# Control.net
KiCad netlist of a schematic drawn in Altium Designer
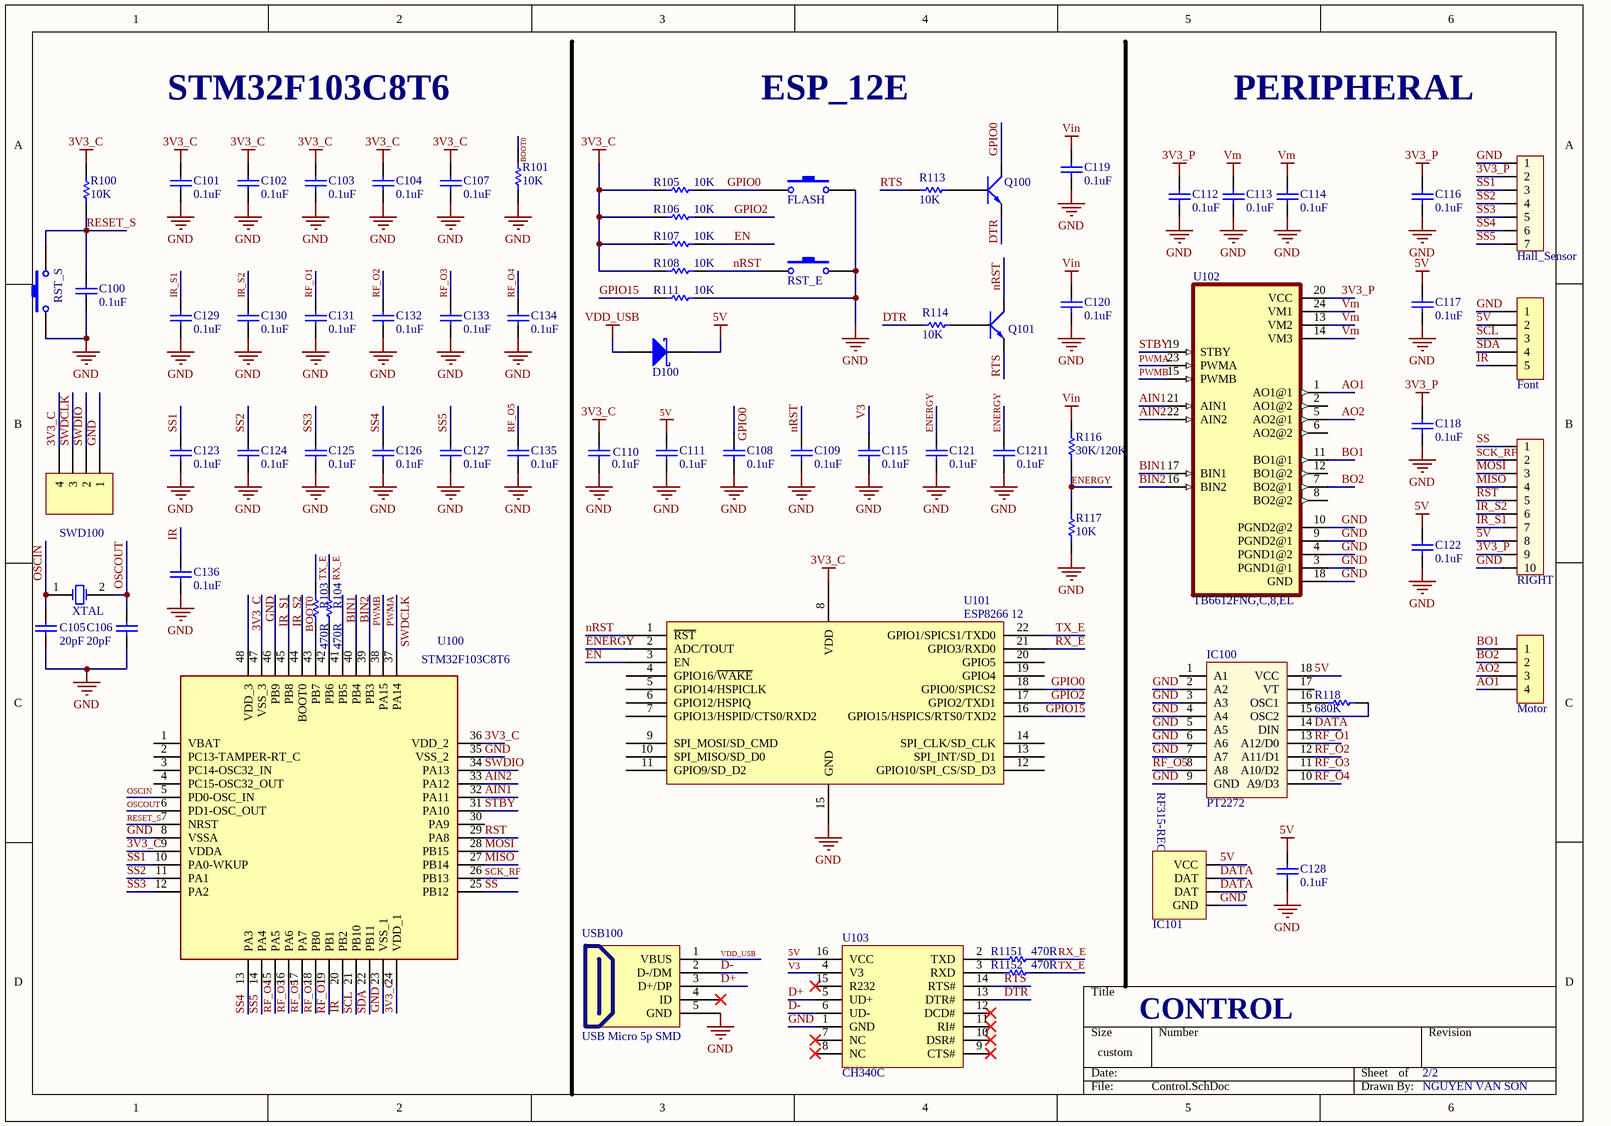
[diagram p0: Control.SchDoc]

(export (version "E")
  (design (tool "Eeschema 10.0.6"))
  (components
    (comp (ref "C100")
      (value "0.1uF")
      (footprint "CAP-SM-0603")
      (description "Capacitor")
      (fields (field (name "Comment") "Cap Non-Pol SMD"))
      (libsource (lib "PIF_Library") (part "Cap Non-Pol SMD"))
    )
    (comp (ref "C101")
      (value "0.1uF")
      (footprint "CAP-SM-0603")
      (description "Capacitor")
      (fields (field (name "Comment") "Cap Non-Pol SMD"))
      (libsource (lib "PIF_Library") (part "Cap Non-Pol SMD"))
    )
    (comp (ref "C102")
      (value "0.1uF")
      (footprint "CAP-SM-0603")
      (description "Capacitor")
      (fields (field (name "Comment") "Cap Non-Pol SMD"))
      (libsource (lib "PIF_Library") (part "Cap Non-Pol SMD"))
    )
    (comp (ref "C103")
      (value "0.1uF")
      (footprint "CAP-SM-0603")
      (description "Capacitor")
      (fields (field (name "Comment") "Cap Non-Pol SMD"))
      (libsource (lib "PIF_Library") (part "Cap Non-Pol SMD"))
    )
    (comp (ref "C104")
      (value "0.1uF")
      (footprint "CAP-SM-0603")
      (description "Capacitor")
      (fields (field (name "Comment") "Cap Non-Pol SMD"))
      (libsource (lib "PIF_Library") (part "Cap Non-Pol SMD"))
    )
    (comp (ref "C105")
      (value "20pF")
      (footprint "CAP-SM-0603")
      (description "Capacitor")
      (fields (field (name "Comment") "Cap Non-Pol SMD"))
      (libsource (lib "PIF_Library") (part "Cap Non-Pol SMD"))
    )
    (comp (ref "C106")
      (value "20pF")
      (footprint "CAP-SM-0603")
      (description "Capacitor")
      (fields (field (name "Comment") "Cap Non-Pol SMD"))
      (libsource (lib "PIF_Library") (part "Cap Non-Pol SMD"))
    )
    (comp (ref "C107")
      (value "0.1uF")
      (footprint "CAP-SM-0603")
      (description "Capacitor")
      (fields (field (name "Comment") "Cap Non-Pol SMD"))
      (libsource (lib "PIF_Library") (part "Cap Non-Pol SMD"))
    )
    (comp (ref "C108")
      (value "0.1uF")
      (footprint "CAP-SM-0603")
      (description "Capacitor")
      (fields (field (name "Comment") "Cap Non-Pol SMD"))
      (libsource (lib "PIF_Library") (part "Cap Non-Pol SMD"))
    )
    (comp (ref "C109")
      (value "0.1uF")
      (footprint "CAP-SM-0603")
      (description "Capacitor")
      (fields (field (name "Comment") "Cap Non-Pol SMD"))
      (libsource (lib "PIF_Library") (part "Cap Non-Pol SMD"))
    )
    (comp (ref "C110")
      (value "0.1uF")
      (footprint "CAP-SM-0603")
      (description "Capacitor")
      (fields (field (name "Comment") "Cap Non-Pol SMD"))
      (libsource (lib "PIF_Library") (part "Cap Non-Pol SMD"))
    )
    (comp (ref "C111")
      (value "0.1uF")
      (footprint "CAP-SM-0603")
      (description "Capacitor")
      (fields (field (name "Comment") "Cap Non-Pol SMD"))
      (libsource (lib "PIF_Library") (part "Cap Non-Pol SMD"))
    )
    (comp (ref "C112")
      (value "0.1uF")
      (footprint "CAP-SM-0603")
      (description "Capacitor")
      (fields (field (name "Comment") "Cap Non-Pol SMD"))
      (libsource (lib "PIF_Library") (part "Cap Non-Pol SMD"))
    )
    (comp (ref "C113")
      (value "0.1uF")
      (footprint "CAP-SM-0603")
      (description "Capacitor")
      (fields (field (name "Comment") "Cap Non-Pol SMD"))
      (libsource (lib "PIF_Library") (part "Cap Non-Pol SMD"))
    )
    (comp (ref "C114")
      (value "0.1uF")
      (footprint "CAP-SM-0603")
      (description "Capacitor")
      (fields (field (name "Comment") "Cap Non-Pol SMD"))
      (libsource (lib "PIF_Library") (part "Cap Non-Pol SMD"))
    )
    (comp (ref "C115")
      (value "0.1uF")
      (footprint "CAP-SM-0603")
      (description "Capacitor")
      (fields (field (name "Comment") "Cap Non-Pol SMD"))
      (libsource (lib "PIF_Library") (part "Cap Non-Pol SMD"))
    )
    (comp (ref "C116")
      (value "0.1uF")
      (footprint "CAP-SM-0603")
      (description "Capacitor")
      (fields (field (name "Comment") "Cap Non-Pol SMD"))
      (libsource (lib "PIF_Library") (part "Cap Non-Pol SMD"))
    )
    (comp (ref "C117")
      (value "0.1uF")
      (footprint "CAP-SM-0603")
      (description "Capacitor")
      (fields (field (name "Comment") "Cap Non-Pol SMD"))
      (libsource (lib "PIF_Library") (part "Cap Non-Pol SMD"))
    )
    (comp (ref "C118")
      (value "0.1uF")
      (footprint "CAP-SM-0603")
      (description "Capacitor")
      (fields (field (name "Comment") "Cap Non-Pol SMD"))
      (libsource (lib "PIF_Library") (part "Cap Non-Pol SMD"))
    )
    (comp (ref "C119")
      (value "0.1uF")
      (footprint "CAP-SM-0603")
      (description "Capacitor")
      (fields (field (name "Comment") "Cap Non-Pol SMD"))
      (libsource (lib "PIF_Library") (part "Cap Non-Pol SMD"))
    )
    (comp (ref "C120")
      (value "0.1uF")
      (footprint "CAP-SM-0603")
      (description "Capacitor")
      (fields (field (name "Comment") "Cap Non-Pol SMD"))
      (libsource (lib "PIF_Library") (part "Cap Non-Pol SMD"))
    )
    (comp (ref "C121")
      (value "0.1uF")
      (footprint "CAP-SM-0603")
      (description "Capacitor")
      (fields (field (name "Comment") "Cap Non-Pol SMD"))
      (libsource (lib "PIF_Library") (part "Cap Non-Pol SMD"))
    )
    (comp (ref "C122")
      (value "0.1uF")
      (footprint "CAP-SM-0603")
      (description "Capacitor")
      (fields (field (name "Comment") "Cap Non-Pol SMD"))
      (libsource (lib "PIF_Library") (part "Cap Non-Pol SMD"))
    )
    (comp (ref "C123")
      (value "0.1uF")
      (footprint "CAP-SM-0603")
      (description "Capacitor")
      (fields (field (name "Comment") "Cap Non-Pol SMD"))
      (libsource (lib "PIF_Library") (part "Cap Non-Pol SMD"))
    )
    (comp (ref "C124")
      (value "0.1uF")
      (footprint "CAP-SM-0603")
      (description "Capacitor")
      (fields (field (name "Comment") "Cap Non-Pol SMD"))
      (libsource (lib "PIF_Library") (part "Cap Non-Pol SMD"))
    )
    (comp (ref "C125")
      (value "0.1uF")
      (footprint "CAP-SM-0603")
      (description "Capacitor")
      (fields (field (name "Comment") "Cap Non-Pol SMD"))
      (libsource (lib "PIF_Library") (part "Cap Non-Pol SMD"))
    )
    (comp (ref "C126")
      (value "0.1uF")
      (footprint "CAP-SM-0603")
      (description "Capacitor")
      (fields (field (name "Comment") "Cap Non-Pol SMD"))
      (libsource (lib "PIF_Library") (part "Cap Non-Pol SMD"))
    )
    (comp (ref "C127")
      (value "0.1uF")
      (footprint "CAP-SM-0603")
      (description "Capacitor")
      (fields (field (name "Comment") "Cap Non-Pol SMD"))
      (libsource (lib "PIF_Library") (part "Cap Non-Pol SMD"))
    )
    (comp (ref "C128")
      (value "0.1uF")
      (footprint "CAP-SM-0603")
      (description "Capacitor")
      (fields (field (name "Comment") "Cap Non-Pol SMD"))
      (libsource (lib "PIF_Library") (part "Cap Non-Pol SMD"))
    )
    (comp (ref "C129")
      (value "0.1uF")
      (footprint "CAP-SM-0603")
      (description "Capacitor")
      (fields (field (name "Comment") "Cap Non-Pol SMD"))
      (libsource (lib "PIF_Library") (part "Cap Non-Pol SMD"))
    )
    (comp (ref "C130")
      (value "0.1uF")
      (footprint "CAP-SM-0603")
      (description "Capacitor")
      (fields (field (name "Comment") "Cap Non-Pol SMD"))
      (libsource (lib "PIF_Library") (part "Cap Non-Pol SMD"))
    )
    (comp (ref "C131")
      (value "0.1uF")
      (footprint "CAP-SM-0603")
      (description "Capacitor")
      (fields (field (name "Comment") "Cap Non-Pol SMD"))
      (libsource (lib "PIF_Library") (part "Cap Non-Pol SMD"))
    )
    (comp (ref "C132")
      (value "0.1uF")
      (footprint "CAP-SM-0603")
      (description "Capacitor")
      (fields (field (name "Comment") "Cap Non-Pol SMD"))
      (libsource (lib "PIF_Library") (part "Cap Non-Pol SMD"))
    )
    (comp (ref "C133")
      (value "0.1uF")
      (footprint "CAP-SM-0603")
      (description "Capacitor")
      (fields (field (name "Comment") "Cap Non-Pol SMD"))
      (libsource (lib "PIF_Library") (part "Cap Non-Pol SMD"))
    )
    (comp (ref "C134")
      (value "0.1uF")
      (footprint "CAP-SM-0603")
      (description "Capacitor")
      (fields (field (name "Comment") "Cap Non-Pol SMD"))
      (libsource (lib "PIF_Library") (part "Cap Non-Pol SMD"))
    )
    (comp (ref "C135")
      (value "0.1uF")
      (footprint "CAP-SM-0603")
      (description "Capacitor")
      (fields (field (name "Comment") "Cap Non-Pol SMD"))
      (libsource (lib "PIF_Library") (part "Cap Non-Pol SMD"))
    )
    (comp (ref "C136")
      (value "0.1uF")
      (footprint "CAP-SM-0603")
      (description "Capacitor")
      (fields (field (name "Comment") "Cap Non-Pol SMD"))
      (libsource (lib "PIF_Library") (part "Cap Non-Pol SMD"))
    )
    (comp (ref "C1211")
      (value "0.1uF")
      (footprint "CAP-SM-0603")
      (description "Capacitor")
      (fields (field (name "Comment") "Cap Non-Pol SMD"))
      (libsource (lib "PIF_Library") (part "Cap Non-Pol SMD"))
    )
    (comp (ref "D100")
      (value "D Schottky")
      (footprint "SS34")
      (description "Schottky Diode")
      (fields (field (name "PUBLISHER") "Altium Limited"))
      (libsource (lib "PIF_Library") (part "D Schottky"))
    )
    (comp (ref "FLASH")
      (value "Tact SW - 2Pin")
      (footprint "SW-SMD")
      (description "Switch button 2 pin")
      (libsource (lib "PIF_Library") (part "Tact SW - 2Pin"))
    )
    (comp (ref "H100")
      (value "Hall_Sensor")
      (footprint "Header 7P DC 2.54")
      (description "Cắm")
      (libsource (lib "Altium_Lib_by_KhueNguyenCreator") (part "Header 7P 2.54 Duc Cong"))
    )
    (comp (ref "H101")
      (value "Font")
      (footprint "Header 5P DC 2.54")
      (description "Cắm")
      (libsource (lib "Altium_Lib_by_KhueNguyenCreator") (part "Header 5P 2.54 Duc Cong"))
    )
    (comp (ref "H102")
      (value "RIGHT")
      (footprint "XH2.54M-10")
      (description "Cắm")
      (libsource (lib "Altium_Lib_by_KhueNguyenCreator") (part "Header 10P 2.54 Duc Thang"))
    )
    (comp (ref "H104")
      (value "Motor")
      (footprint "JP 1x4 DT")
      (description "Cắm")
      (libsource (lib "Altium_Lib_by_KhueNguyenCreator") (part "Header 4P 2.54 Duc Cong"))
    )
    (comp (ref "IC100")
      (value "PT2272")
      (footprint "DIP18")
      (description "Remote Control Decoder")
      (libsource (lib "TechMT.VN_Lib_Project v2") (part "PT2272"))
    )
    (comp (ref "IC101")
      (value "RF315-RECEIVE-NOIC")
      (footprint "RF315-RECEIVE-NOIC")
      (fields
        (field (name "MANUFACTURER") "Würth Elektronik eiSos GmbH")
        (field (name "PARTNO") "613004143121")
        (field (name "CREATED BY") "Karrer Zheng")
      )
      (libsource (lib "TechMT.VN_Lib_Project v2") (part "RF315-RECEIVE-NOIC"))
    )
    (comp (ref "Q100")
      (value "HF")
      (footprint "SOT23")
      (description "NPN transistor")
      (libsource (lib "Altium_Lib_by_KhueNguyenCreator") (part "C1815 HF SMD"))
    )
    (comp (ref "Q101")
      (value "HF")
      (footprint "SOT23")
      (description "NPN transistor")
      (libsource (lib "Altium_Lib_by_KhueNguyenCreator") (part "C1815 HF SMD"))
    )
    (comp (ref "R100")
      (value "10K")
      (footprint "RES-SM-0603")
      (description "Resistor")
      (fields (field (name "Comment") "RESISTOR SMD"))
      (libsource (lib "PIF_Library") (part "RESISTOR SMD"))
    )
    (comp (ref "R101")
      (value "10K")
      (footprint "RES-SM-0603")
      (description "Resistor")
      (fields (field (name "Comment") "RESISTOR SMD"))
      (libsource (lib "PIF_Library") (part "RESISTOR SMD"))
    )
    (comp (ref "R103")
      (value "470R")
      (footprint "RES-SM-0603")
      (description "Resistor")
      (fields (field (name "Comment") "RESISTOR SMD"))
      (libsource (lib "PIF_Library") (part "RESISTOR SMD"))
    )
    (comp (ref "R104")
      (value "470R")
      (footprint "RES-SM-0603")
      (description "Resistor")
      (fields (field (name "Comment") "RESISTOR SMD"))
      (libsource (lib "PIF_Library") (part "RESISTOR SMD"))
    )
    (comp (ref "R105")
      (value "10K")
      (footprint "RES-SM-0603")
      (description "Resistor")
      (fields (field (name "Comment") "RESISTOR SMD"))
      (libsource (lib "PIF_Library") (part "RESISTOR SMD"))
    )
    (comp (ref "R106")
      (value "10K")
      (footprint "RES-SM-0603")
      (description "Resistor")
      (fields (field (name "Comment") "RESISTOR SMD"))
      (libsource (lib "PIF_Library") (part "RESISTOR SMD"))
    )
    (comp (ref "R107")
      (value "10K")
      (footprint "RES-SM-0603")
      (description "Resistor")
      (fields (field (name "Comment") "RESISTOR SMD"))
      (libsource (lib "PIF_Library") (part "RESISTOR SMD"))
    )
    (comp (ref "R108")
      (value "10K")
      (footprint "RES-SM-0603")
      (description "Resistor")
      (fields (field (name "Comment") "RESISTOR SMD"))
      (libsource (lib "PIF_Library") (part "RESISTOR SMD"))
    )
    (comp (ref "R111")
      (value "10K")
      (footprint "RES-SM-0603")
      (description "Resistor")
      (fields (field (name "Comment") "RESISTOR SMD"))
      (libsource (lib "PIF_Library") (part "RESISTOR SMD"))
    )
    (comp (ref "R113")
      (value "10K")
      (footprint "RES-SM-0603")
      (description "Resistor")
      (fields (field (name "Comment") "RESISTOR SMD"))
      (libsource (lib "PIF_Library") (part "RESISTOR SMD"))
    )
    (comp (ref "R114")
      (value "10K")
      (footprint "RES-SM-0603")
      (description "Resistor")
      (fields (field (name "Comment") "RESISTOR SMD"))
      (libsource (lib "PIF_Library") (part "RESISTOR SMD"))
    )
    (comp (ref "R116")
      (value "30K/120K")
      (footprint "RES-SM-0603")
      (description "Resistor")
      (fields (field (name "Comment") "RESISTOR SMD"))
      (libsource (lib "PIF_Library") (part "RESISTOR SMD"))
    )
    (comp (ref "R117")
      (value "10K")
      (footprint "RES-SM-0603")
      (description "Resistor")
      (fields (field (name "Comment") "RESISTOR SMD"))
      (libsource (lib "PIF_Library") (part "RESISTOR SMD"))
    )
    (comp (ref "R118")
      (value "680K")
      (footprint "RES-SM-0603")
      (description "Resistor")
      (fields (field (name "Comment") "RESISTOR SMD"))
      (libsource (lib "PIF_Library") (part "RESISTOR SMD"))
    )
    (comp (ref "R1151")
      (value "470R")
      (footprint "RES-SM-0603")
      (description "Resistor")
      (fields (field (name "Comment") "RESISTOR SMD"))
      (libsource (lib "PIF_Library") (part "RESISTOR SMD"))
    )
    (comp (ref "R1152")
      (value "470R")
      (footprint "RES-SM-0603")
      (description "Resistor")
      (fields (field (name "Comment") "RESISTOR SMD"))
      (libsource (lib "PIF_Library") (part "RESISTOR SMD"))
    )
    (comp (ref "RST_E")
      (value "Tact SW - 2Pin")
      (footprint "SW-SMD")
      (description "Switch button 2 pin")
      (libsource (lib "PIF_Library") (part "Tact SW - 2Pin"))
    )
    (comp (ref "RST_S")
      (value "Tact SW - 2Pin")
      (footprint "SW-SMD")
      (description "Switch button 2 pin")
      (libsource (lib "PIF_Library") (part "Tact SW - 2Pin"))
    )
    (comp (ref "SWD100")
      (value "Header 4H")
      (footprint "JP4")
      (description "Header, 4-Pin, Right Angle")
      (fields (field (name "PUBLISHER") "Altium Limited"))
      (libsource (lib "PIF_Library") (part "Header 4H"))
    )
    (comp (ref "U100")
      (value "STM32F103C8T6")
      (footprint "LQFP-48_19.6_393_58X11_SMD")
      (description "ARM® Cortex®-M3 STM32F1 Microcontroller IC 32-Bit 72MHz 64KB (64K x 8) FLASH 48-LQFP (7x7)")
      (fields (field (name "MANUFACTURER") "STMicroelectronics"))
      (libsource (lib "Altium_Lib_by_KhueNguyenCreator") (part "IC_STM32F103C8T6"))
    )
    (comp (ref "U101")
      (value "ESP8266 12")
      (footprint "ESP8266 12")
      (description "ESP8266 12 22 Pin")
      (libsource (lib "Altium_Lib_by_KhueNguyenCreator") (part "ESP8266 12"))
    )
    (comp (ref "U102")
      (value "TB6612FNG,C,8,EL")
      (footprint "SOP65P760X160-24N")
      (description "- Motor Driver Power MOSFET Parallel 24-SSOP")
      (fields (field (name "MF") "Toshiba"))
      (libsource (lib "TB6612FNG_C_8_EL") (part "TB6612FNG,C,8,EL"))
    )
    (comp (ref "U103")
      (value "CH340C")
      (footprint "SOIC16_50_284_25X90_SMT")
      (description "USB Bridge, USB to UART USB 2.0 UART Interface")
      (fields (field (name "MANUFACTURER") "Olimex"))
      (libsource (lib "Altium_Lib_by_KhueNguyenCreator") (part "IC_CH340C"))
    )
    (comp (ref "USB100")
      (value "USB Micro 5p SMD")
      (footprint "USB Micro 5p SMD")
      (description "USB Type B")
      (libsource (lib "Altium_Lib_by_KhueNguyenCreator") (part "USB Micro 5p SMD"))
    )
    (comp (ref "XTAL")
      (value "XTAL")
      (footprint "XT2")
      (description "Crystal Oscillator")
      (fields (field (name "PUBLISHER") "Altium Limited"))
      (libsource (lib "PIF_Library") (part "XTAL"))
    )
  )
  (nets
    (net (code "1") (name "/AIN1") (class "Default")
      (node (ref "U100") (pin "32") (pinfunction "PA11_32") (pintype "passive"))
      (node (ref "U102") (pin "21") (pinfunction "AIN1_21") (pintype "input"))
    )
    (net (code "2") (name "/AIN2") (class "Default")
      (node (ref "U100") (pin "33") (pinfunction "PA12_33") (pintype "passive"))
      (node (ref "U102") (pin "22") (pinfunction "AIN2_22") (pintype "input"))
    )
    (net (code "3") (name "/AO1") (class "Default")
      (node (ref "H104") (pin "4") (pinfunction "4_4") (pintype "passive"))
      (node (ref "U102") (pin "1") (pinfunction "AO1@1_1") (pintype "output"))
    )
    (net (code "4") (name "/AO2") (class "Default")
      (node (ref "H104") (pin "3") (pinfunction "3_3") (pintype "passive"))
      (node (ref "U102") (pin "5") (pinfunction "AO2@1_5") (pintype "output"))
    )
    (net (code "5") (name "/BIN1") (class "Default")
      (node (ref "U100") (pin "41") (pinfunction "PB5_41") (pintype "passive"))
      (node (ref "U102") (pin "17") (pinfunction "BIN1_17") (pintype "input"))
    )
    (net (code "6") (name "/BIN2") (class "Default")
      (node (ref "U100") (pin "40") (pinfunction "PB4_40") (pintype "passive"))
      (node (ref "U102") (pin "16") (pinfunction "BIN2_16") (pintype "input"))
    )
    (net (code "7") (name "/BO1") (class "Default")
      (node (ref "H104") (pin "1") (pinfunction "1_1") (pintype "passive"))
      (node (ref "U102") (pin "11") (pinfunction "BO1@1_11") (pintype "output"))
    )
    (net (code "8") (name "/BO2") (class "Default")
      (node (ref "H104") (pin "2") (pinfunction "2_2") (pintype "passive"))
      (node (ref "U102") (pin "7") (pinfunction "BO2@1_7") (pintype "output"))
    )
    (net (code "9") (name "/BOOT0") (class "Default")
      (node (ref "R101") (pin "1") (pinfunction "1_1") (pintype "passive"))
      (node (ref "U100") (pin "44") (pinfunction "BOOT0_44") (pintype "passive"))
    )
    (net (code "10") (name "/D+") (class "Default")
      (node (ref "U103") (pin "5") (pinfunction "UD+_5") (pintype "passive"))
      (node (ref "USB100") (pin "3") (pinfunction "D+/DP_3") (pintype "passive"))
    )
    (net (code "11") (name "/D-") (class "Default")
      (node (ref "U103") (pin "6") (pinfunction "UD-_6") (pintype "passive"))
      (node (ref "USB100") (pin "2") (pinfunction "D-/DM_2") (pintype "passive"))
    )
    (net (code "12") (name "/DATA") (class "Default")
      (node (ref "IC100") (pin "14") (pinfunction "DIN_14") (pintype "passive"))
      (node (ref "IC101") (pin "2") (pinfunction "DAT_2") (pintype "passive"))
      (node (ref "IC101") (pin "3") (pinfunction "DAT_3") (pintype "passive"))
    )
    (net (code "13") (name "/DTR") (class "Default")
      (node (ref "Q100") (pin "2") (pinfunction "E_2") (pintype "passive"))
      (node (ref "R114") (pin "1") (pinfunction "1_1") (pintype "passive"))
      (node (ref "U103") (pin "13") (pinfunction "DTR#_13") (pintype "passive"))
    )
    (net (code "14") (name "/EN") (class "Default")
      (node (ref "R107") (pin "1") (pinfunction "1_1") (pintype "passive"))
      (node (ref "U101") (pin "3") (pinfunction "EN_3") (pintype "passive"))
    )
    (net (code "15") (name "/ENERGY") (class "Default")
      (node (ref "C121") (pin "2") (pinfunction "2_2") (pintype "passive"))
      (node (ref "C1211") (pin "2") (pinfunction "2_2") (pintype "passive"))
      (node (ref "R116") (pin "1") (pinfunction "1_1") (pintype "passive"))
      (node (ref "R117") (pin "2") (pinfunction "2_2") (pintype "passive"))
      (node (ref "U101") (pin "2") (pinfunction "ADC/TOUT_2") (pintype "passive"))
    )
    (net (code "16") (name "/GPIO0") (class "Default")
      (node (ref "C108") (pin "2") (pinfunction "2_2") (pintype "passive"))
      (node (ref "FLASH") (pin "2") (pinfunction "2_2") (pintype "passive"))
      (node (ref "Q100") (pin "3") (pinfunction "C_3") (pintype "passive"))
      (node (ref "R105") (pin "1") (pinfunction "1_1") (pintype "passive"))
      (node (ref "U101") (pin "18") (pinfunction "GPIO0/SPICS2_18") (pintype "passive"))
    )
    (net (code "17") (name "/GPIO2") (class "Default")
      (node (ref "R106") (pin "1") (pinfunction "1_1") (pintype "passive"))
      (node (ref "U101") (pin "17") (pinfunction "GPIO2/TXD1_17") (pintype "passive"))
    )
    (net (code "18") (name "/GPIO15") (class "Default")
      (node (ref "R111") (pin "2") (pinfunction "2_2") (pintype "passive"))
      (node (ref "U101") (pin "16") (pinfunction "GPIO15/HSPICS/RTS0/TXD2_16") (pintype "passive"))
    )
    (net (code "19") (name "/IR") (class "Default")
      (node (ref "C136") (pin "2") (pinfunction "2_2") (pintype "passive"))
      (node (ref "H101") (pin "5") (pinfunction "5_5") (pintype "passive"))
      (node (ref "U100") (pin "20") (pinfunction "PB2_20") (pintype "passive"))
    )
    (net (code "20") (name "/IR_S1") (class "Default")
      (node (ref "C129") (pin "2") (pinfunction "2_2") (pintype "passive"))
      (node (ref "H102") (pin "7") (pinfunction "7_7") (pintype "passive"))
      (node (ref "U100") (pin "46") (pinfunction "PB9_46") (pintype "passive"))
    )
    (net (code "21") (name "/IR_S2") (class "Default")
      (node (ref "C130") (pin "2") (pinfunction "2_2") (pintype "passive"))
      (node (ref "H102") (pin "6") (pinfunction "6_6") (pintype "passive"))
      (node (ref "U100") (pin "45") (pinfunction "PB8_45") (pintype "passive"))
    )
    (net (code "22") (name "/MISO") (class "Default")
      (node (ref "H102") (pin "4") (pinfunction "4_4") (pintype "passive"))
      (node (ref "U100") (pin "27") (pinfunction "PB14_27") (pintype "passive"))
    )
    (net (code "23") (name "/MOSI") (class "Default")
      (node (ref "H102") (pin "3") (pinfunction "3_3") (pintype "passive"))
      (node (ref "U100") (pin "28") (pinfunction "PB15_28") (pintype "passive"))
    )
    (net (code "24") (name "/OSCIN") (class "Default")
      (node (ref "C105") (pin "2") (pinfunction "2_2") (pintype "passive"))
      (node (ref "U100") (pin "5") (pinfunction "PD0-OSC_IN_5") (pintype "passive"))
      (node (ref "XTAL") (pin "1") (pinfunction "OSC1_1") (pintype "passive"))
    )
    (net (code "25") (name "/OSCOUT") (class "Default")
      (node (ref "C106") (pin "2") (pinfunction "2_2") (pintype "passive"))
      (node (ref "U100") (pin "6") (pinfunction "PD1-OSC_OUT_6") (pintype "passive"))
      (node (ref "XTAL") (pin "2") (pinfunction "OSC2_2") (pintype "passive"))
    )
    (net (code "26") (name "/PWMA") (class "Default")
      (node (ref "U100") (pin "38") (pinfunction "PA15_38") (pintype "passive"))
      (node (ref "U102") (pin "23") (pinfunction "PWMA_23") (pintype "input"))
    )
    (net (code "27") (name "/PWMB") (class "Default")
      (node (ref "U100") (pin "39") (pinfunction "PB3_39") (pintype "passive"))
      (node (ref "U102") (pin "15") (pinfunction "PWMB_15") (pintype "input"))
    )
    (net (code "28") (name "/RESET_S") (class "Default")
      (node (ref "C100") (pin "2") (pinfunction "2_2") (pintype "passive"))
      (node (ref "R100") (pin "1") (pinfunction "1_1") (pintype "passive"))
      (node (ref "RST_S") (pin "2") (pinfunction "2_2") (pintype "passive"))
      (node (ref "U100") (pin "7") (pinfunction "NRST_7") (pintype "passive"))
    )
    (net (code "29") (name "/RF_O1") (class "Default")
      (node (ref "C131") (pin "2") (pinfunction "2_2") (pintype "passive"))
      (node (ref "IC100") (pin "13") (pinfunction "A12/D0_13") (pintype "passive"))
      (node (ref "U100") (pin "19") (pinfunction "PB1_19") (pintype "passive"))
    )
    (net (code "30") (name "/RF_O2") (class "Default")
      (node (ref "C132") (pin "2") (pinfunction "2_2") (pintype "passive"))
      (node (ref "IC100") (pin "12") (pinfunction "A11/D1_12") (pintype "passive"))
      (node (ref "U100") (pin "18") (pinfunction "PB0_18") (pintype "passive"))
    )
    (net (code "31") (name "/RF_O3") (class "Default")
      (node (ref "C133") (pin "2") (pinfunction "2_2") (pintype "passive"))
      (node (ref "IC100") (pin "11") (pinfunction "A10/D2_11") (pintype "passive"))
      (node (ref "U100") (pin "16") (pinfunction "PA6_16") (pintype "passive"))
    )
    (net (code "32") (name "/RF_O4") (class "Default")
      (node (ref "C134") (pin "2") (pinfunction "2_2") (pintype "passive"))
      (node (ref "IC100") (pin "10") (pinfunction "A9/D3_10") (pintype "passive"))
      (node (ref "U100") (pin "15") (pinfunction "PA5_15") (pintype "passive"))
    )
    (net (code "33") (name "/RF_O5") (class "Default")
      (node (ref "C135") (pin "2") (pinfunction "2_2") (pintype "passive"))
      (node (ref "IC100") (pin "8") (pinfunction "A8_8") (pintype "passive"))
      (node (ref "U100") (pin "17") (pinfunction "PA7_17") (pintype "passive"))
    )
    (net (code "34") (name "/RST") (class "Default")
      (node (ref "H102") (pin "5") (pinfunction "5_5") (pintype "passive"))
      (node (ref "U100") (pin "29") (pinfunction "PA8_29") (pintype "passive"))
    )
    (net (code "35") (name "/RTS") (class "Default")
      (node (ref "Q101") (pin "2") (pinfunction "E_2") (pintype "passive"))
      (node (ref "R113") (pin "1") (pinfunction "1_1") (pintype "passive"))
      (node (ref "U103") (pin "14") (pinfunction "RTS#_14") (pintype "passive"))
    )
    (net (code "36") (name "/RX_E") (class "Default")
      (node (ref "R104") (pin "2") (pinfunction "2_2") (pintype "passive"))
      (node (ref "R1151") (pin "1") (pinfunction "1_1") (pintype "passive"))
      (node (ref "U101") (pin "21") (pinfunction "GPIO3/RXD0_21") (pintype "passive"))
    )
    (net (code "37") (name "/SCK_RF") (class "Default")
      (node (ref "H102") (pin "2") (pinfunction "2_2") (pintype "passive"))
      (node (ref "U100") (pin "26") (pinfunction "PB13_26") (pintype "passive"))
    )
    (net (code "38") (name "/SCL") (class "Default")
      (node (ref "H101") (pin "3") (pinfunction "3_3") (pintype "passive"))
      (node (ref "U100") (pin "21") (pinfunction "PB10_21") (pintype "passive"))
    )
    (net (code "39") (name "/SDA") (class "Default")
      (node (ref "H101") (pin "4") (pinfunction "4_4") (pintype "passive"))
      (node (ref "U100") (pin "22") (pinfunction "PB11_22") (pintype "passive"))
    )
    (net (code "40") (name "/SS") (class "Default")
      (node (ref "H102") (pin "1") (pinfunction "1_1") (pintype "passive"))
      (node (ref "U100") (pin "25") (pinfunction "PB12_25") (pintype "passive"))
    )
    (net (code "41") (name "/SS1") (class "Default")
      (node (ref "C123") (pin "2") (pinfunction "2_2") (pintype "passive"))
      (node (ref "H100") (pin "3") (pinfunction "3_3") (pintype "passive"))
      (node (ref "U100") (pin "10") (pinfunction "PA0-WKUP_10") (pintype "passive"))
    )
    (net (code "42") (name "/SS2") (class "Default")
      (node (ref "C124") (pin "2") (pinfunction "2_2") (pintype "passive"))
      (node (ref "H100") (pin "4") (pinfunction "4_4") (pintype "passive"))
      (node (ref "U100") (pin "11") (pinfunction "PA1_11") (pintype "passive"))
    )
    (net (code "43") (name "/SS3") (class "Default")
      (node (ref "C125") (pin "2") (pinfunction "2_2") (pintype "passive"))
      (node (ref "H100") (pin "5") (pinfunction "5_5") (pintype "passive"))
      (node (ref "U100") (pin "12") (pinfunction "PA2_12") (pintype "passive"))
    )
    (net (code "44") (name "/SS4") (class "Default")
      (node (ref "C126") (pin "2") (pinfunction "2_2") (pintype "passive"))
      (node (ref "H100") (pin "6") (pinfunction "6_6") (pintype "passive"))
      (node (ref "U100") (pin "13") (pinfunction "PA3_13") (pintype "passive"))
    )
    (net (code "45") (name "/SS5") (class "Default")
      (node (ref "C127") (pin "2") (pinfunction "2_2") (pintype "passive"))
      (node (ref "H100") (pin "7") (pinfunction "7_7") (pintype "passive"))
      (node (ref "U100") (pin "14") (pinfunction "PA4_14") (pintype "passive"))
    )
    (net (code "46") (name "/STBY") (class "Default")
      (node (ref "U100") (pin "31") (pinfunction "PA10_31") (pintype "passive"))
      (node (ref "U102") (pin "19") (pinfunction "STBY_19") (pintype "input"))
    )
    (net (code "47") (name "/SWDCLK") (class "Default")
      (node (ref "SWD100") (pin "3") (pinfunction "3_3") (pintype "passive"))
      (node (ref "U100") (pin "37") (pinfunction "PA14_37") (pintype "passive"))
    )
    (net (code "48") (name "/SWDIO") (class "Default")
      (node (ref "SWD100") (pin "2") (pinfunction "2_2") (pintype "passive"))
      (node (ref "U100") (pin "34") (pinfunction "PA13_34") (pintype "passive"))
    )
    (net (code "49") (name "/TX_E") (class "Default")
      (node (ref "R103") (pin "2") (pinfunction "2_2") (pintype "passive"))
      (node (ref "R1152") (pin "1") (pinfunction "1_1") (pintype "passive"))
      (node (ref "U101") (pin "22") (pinfunction "GPIO1/SPICS1/TXD0_22") (pintype "passive"))
    )
    (net (code "50") (name "/V3") (class "Default")
      (node (ref "C115") (pin "2") (pinfunction "2_2") (pintype "passive"))
      (node (ref "U103") (pin "4") (pinfunction "V3_4") (pintype "passive"))
    )
    (net (code "51") (name "/nRST") (class "Default")
      (node (ref "C109") (pin "2") (pinfunction "2_2") (pintype "passive"))
      (node (ref "Q101") (pin "3") (pinfunction "C_3") (pintype "passive"))
      (node (ref "R108") (pin "1") (pinfunction "1_1") (pintype "passive"))
      (node (ref "RST_E") (pin "2") (pinfunction "2_2") (pintype "passive"))
      (node (ref "U101") (pin "1") (pinfunction "~{RST}_1") (pintype "passive"))
    )
    (net (code "52") (name "3V3_C") (class "Default")
      (node (ref "C101") (pin "2") (pinfunction "2_2") (pintype "passive"))
      (node (ref "C102") (pin "2") (pinfunction "2_2") (pintype "passive"))
      (node (ref "C103") (pin "2") (pinfunction "2_2") (pintype "passive"))
      (node (ref "C104") (pin "2") (pinfunction "2_2") (pintype "passive"))
      (node (ref "C107") (pin "2") (pinfunction "2_2") (pintype "passive"))
      (node (ref "C110") (pin "2") (pinfunction "2_2") (pintype "passive"))
      (node (ref "R100") (pin "2") (pinfunction "2_2") (pintype "passive"))
      (node (ref "R105") (pin "2") (pinfunction "2_2") (pintype "passive"))
      (node (ref "R106") (pin "2") (pinfunction "2_2") (pintype "passive"))
      (node (ref "R107") (pin "2") (pinfunction "2_2") (pintype "passive"))
      (node (ref "R108") (pin "2") (pinfunction "2_2") (pintype "passive"))
      (node (ref "SWD100") (pin "4") (pinfunction "4_4") (pintype "passive"))
      (node (ref "U100") (pin "24") (pinfunction "VDD_1_24") (pintype "passive"))
      (node (ref "U100") (pin "36") (pinfunction "VDD_2_36") (pintype "passive"))
      (node (ref "U100") (pin "48") (pinfunction "VDD_3_48") (pintype "passive"))
      (node (ref "U100") (pin "9") (pinfunction "VDDA_9") (pintype "passive"))
      (node (ref "U101") (pin "8") (pinfunction "VDD_8") (pintype "passive"))
    )
    (net (code "53") (name "3V3_P") (class "Default")
      (node (ref "C112") (pin "2") (pinfunction "2_2") (pintype "passive"))
      (node (ref "C116") (pin "2") (pinfunction "2_2") (pintype "passive"))
      (node (ref "C118") (pin "2") (pinfunction "2_2") (pintype "passive"))
      (node (ref "H100") (pin "2") (pinfunction "2_2") (pintype "passive"))
      (node (ref "H102") (pin "9") (pinfunction "9_9") (pintype "passive"))
      (node (ref "U102") (pin "20") (pinfunction "VCC_20") (pintype "power_in"))
    )
    (net (code "54") (name "5V") (class "Default")
      (node (ref "C111") (pin "2") (pinfunction "2_2") (pintype "passive"))
      (node (ref "C117") (pin "2") (pinfunction "2_2") (pintype "passive"))
      (node (ref "C122") (pin "2") (pinfunction "2_2") (pintype "passive"))
      (node (ref "C128") (pin "2") (pinfunction "2_2") (pintype "passive"))
      (node (ref "D100") (pin "2") (pinfunction "K_2") (pintype "passive"))
      (node (ref "H101") (pin "2") (pinfunction "2_2") (pintype "passive"))
      (node (ref "H102") (pin "8") (pinfunction "8_8") (pintype "passive"))
      (node (ref "IC100") (pin "18") (pinfunction "VCC_18") (pintype "passive"))
      (node (ref "IC101") (pin "1") (pinfunction "VCC_1") (pintype "passive"))
      (node (ref "U103") (pin "16") (pinfunction "VCC_16") (pintype "passive"))
    )
    (net (code "55") (name "GND") (class "Default")
      (node (ref "C100") (pin "1") (pinfunction "1_1") (pintype "passive"))
      (node (ref "C101") (pin "1") (pinfunction "1_1") (pintype "passive"))
      (node (ref "C102") (pin "1") (pinfunction "1_1") (pintype "passive"))
      (node (ref "C103") (pin "1") (pinfunction "1_1") (pintype "passive"))
      (node (ref "C104") (pin "1") (pinfunction "1_1") (pintype "passive"))
      (node (ref "C105") (pin "1") (pinfunction "1_1") (pintype "passive"))
      (node (ref "C106") (pin "1") (pinfunction "1_1") (pintype "passive"))
      (node (ref "C107") (pin "1") (pinfunction "1_1") (pintype "passive"))
      (node (ref "C108") (pin "1") (pinfunction "1_1") (pintype "passive"))
      (node (ref "C109") (pin "1") (pinfunction "1_1") (pintype "passive"))
      (node (ref "C110") (pin "1") (pinfunction "1_1") (pintype "passive"))
      (node (ref "C111") (pin "1") (pinfunction "1_1") (pintype "passive"))
      (node (ref "C112") (pin "1") (pinfunction "1_1") (pintype "passive"))
      (node (ref "C113") (pin "1") (pinfunction "1_1") (pintype "passive"))
      (node (ref "C114") (pin "1") (pinfunction "1_1") (pintype "passive"))
      (node (ref "C115") (pin "1") (pinfunction "1_1") (pintype "passive"))
      (node (ref "C116") (pin "1") (pinfunction "1_1") (pintype "passive"))
      (node (ref "C117") (pin "1") (pinfunction "1_1") (pintype "passive"))
      (node (ref "C118") (pin "1") (pinfunction "1_1") (pintype "passive"))
      (node (ref "C119") (pin "1") (pinfunction "1_1") (pintype "passive"))
      (node (ref "C120") (pin "1") (pinfunction "1_1") (pintype "passive"))
      (node (ref "C121") (pin "1") (pinfunction "1_1") (pintype "passive"))
      (node (ref "C1211") (pin "1") (pinfunction "1_1") (pintype "passive"))
      (node (ref "C122") (pin "1") (pinfunction "1_1") (pintype "passive"))
      (node (ref "C123") (pin "1") (pinfunction "1_1") (pintype "passive"))
      (node (ref "C124") (pin "1") (pinfunction "1_1") (pintype "passive"))
      (node (ref "C125") (pin "1") (pinfunction "1_1") (pintype "passive"))
      (node (ref "C126") (pin "1") (pinfunction "1_1") (pintype "passive"))
      (node (ref "C127") (pin "1") (pinfunction "1_1") (pintype "passive"))
      (node (ref "C128") (pin "1") (pinfunction "1_1") (pintype "passive"))
      (node (ref "C129") (pin "1") (pinfunction "1_1") (pintype "passive"))
      (node (ref "C130") (pin "1") (pinfunction "1_1") (pintype "passive"))
      (node (ref "C131") (pin "1") (pinfunction "1_1") (pintype "passive"))
      (node (ref "C132") (pin "1") (pinfunction "1_1") (pintype "passive"))
      (node (ref "C133") (pin "1") (pinfunction "1_1") (pintype "passive"))
      (node (ref "C134") (pin "1") (pinfunction "1_1") (pintype "passive"))
      (node (ref "C135") (pin "1") (pinfunction "1_1") (pintype "passive"))
      (node (ref "C136") (pin "1") (pinfunction "1_1") (pintype "passive"))
      (node (ref "FLASH") (pin "1") (pinfunction "1_1") (pintype "passive"))
      (node (ref "H100") (pin "1") (pinfunction "1_1") (pintype "passive"))
      (node (ref "H101") (pin "1") (pinfunction "1_1") (pintype "passive"))
      (node (ref "H102") (pin "10") (pinfunction "10_10") (pintype "passive"))
      (node (ref "IC100") (pin "2") (pinfunction "A2_2") (pintype "passive"))
      (node (ref "IC100") (pin "3") (pinfunction "A3_3") (pintype "passive"))
      (node (ref "IC100") (pin "4") (pinfunction "A4_4") (pintype "passive"))
      (node (ref "IC100") (pin "5") (pinfunction "A5_5") (pintype "passive"))
      (node (ref "IC100") (pin "6") (pinfunction "A6_6") (pintype "passive"))
      (node (ref "IC100") (pin "7") (pinfunction "A7_7") (pintype "passive"))
      (node (ref "IC100") (pin "9") (pinfunction "GND_9") (pintype "passive"))
      (node (ref "IC101") (pin "4") (pinfunction "GND_4") (pintype "passive"))
      (node (ref "R101") (pin "2") (pinfunction "2_2") (pintype "passive"))
      (node (ref "R111") (pin "1") (pinfunction "1_1") (pintype "passive"))
      (node (ref "R117") (pin "1") (pinfunction "1_1") (pintype "passive"))
      (node (ref "RST_E") (pin "1") (pinfunction "1_1") (pintype "passive"))
      (node (ref "RST_S") (pin "1") (pinfunction "1_1") (pintype "passive"))
      (node (ref "SWD100") (pin "1") (pinfunction "1_1") (pintype "passive"))
      (node (ref "U100") (pin "23") (pinfunction "VSS_1_23") (pintype "passive"))
      (node (ref "U100") (pin "35") (pinfunction "VSS_2_35") (pintype "passive"))
      (node (ref "U100") (pin "47") (pinfunction "VSS_3_47") (pintype "passive"))
      (node (ref "U100") (pin "8") (pinfunction "VSSA_8") (pintype "passive"))
      (node (ref "U101") (pin "15") (pinfunction "GND_15") (pintype "passive"))
      (node (ref "U102") (pin "10") (pinfunction "PGND2@2_10") (pintype "passive"))
      (node (ref "U102") (pin "18") (pinfunction "GND_18") (pintype "passive"))
      (node (ref "U102") (pin "3") (pinfunction "PGND1@1_3") (pintype "passive"))
      (node (ref "U102") (pin "4") (pinfunction "PGND1@2_4") (pintype "passive"))
      (node (ref "U102") (pin "9") (pinfunction "PGND2@1_9") (pintype "passive"))
      (node (ref "U103") (pin "1") (pinfunction "GND_1") (pintype "passive"))
      (node (ref "USB100") (pin "5") (pinfunction "GND_5") (pintype "passive"))
    )
    (net (code "56") (name "Net-(IC100-OSC1)") (class "Default")
      (node (ref "IC100") (pin "16") (pinfunction "OSC1_16") (pintype "passive"))
      (node (ref "R118") (pin "2") (pinfunction "2_2") (pintype "passive"))
    )
    (net (code "57") (name "Net-(IC100-OSC2)") (class "Default")
      (node (ref "IC100") (pin "15") (pinfunction "OSC2_15") (pintype "passive"))
      (node (ref "R118") (pin "1") (pinfunction "1_1") (pintype "passive"))
    )
    (net (code "58") (name "Net-(Q100-B)") (class "Default")
      (node (ref "Q100") (pin "1") (pinfunction "B_1") (pintype "passive"))
      (node (ref "R113") (pin "2") (pinfunction "2_2") (pintype "passive"))
    )
    (net (code "59") (name "Net-(Q101-B)") (class "Default")
      (node (ref "Q101") (pin "1") (pinfunction "B_1") (pintype "passive"))
      (node (ref "R114") (pin "2") (pinfunction "2_2") (pintype "passive"))
    )
    (net (code "60") (name "Net-(U100-PB6)") (class "Default")
      (node (ref "R104") (pin "1") (pinfunction "1_1") (pintype "passive"))
      (node (ref "U100") (pin "42") (pinfunction "PB6_42") (pintype "passive"))
    )
    (net (code "61") (name "Net-(U100-PB7)") (class "Default")
      (node (ref "R103") (pin "1") (pinfunction "1_1") (pintype "passive"))
      (node (ref "U100") (pin "43") (pinfunction "PB7_43") (pintype "passive"))
    )
    (net (code "62") (name "Net-(U103-RXD)") (class "Default")
      (node (ref "R1152") (pin "2") (pinfunction "2_2") (pintype "passive"))
      (node (ref "U103") (pin "3") (pinfunction "RXD_3") (pintype "passive"))
    )
    (net (code "63") (name "Net-(U103-TXD)") (class "Default")
      (node (ref "R1151") (pin "2") (pinfunction "2_2") (pintype "passive"))
      (node (ref "U103") (pin "2") (pinfunction "TXD_2") (pintype "passive"))
    )
    (net (code "64") (name "VDD_USB") (class "Default")
      (node (ref "D100") (pin "1") (pinfunction "A_1") (pintype "passive"))
      (node (ref "USB100") (pin "1") (pinfunction "VBUS_1") (pintype "passive"))
    )
    (net (code "65") (name "Vin") (class "Default")
      (node (ref "C119") (pin "2") (pinfunction "2_2") (pintype "passive"))
      (node (ref "C120") (pin "2") (pinfunction "2_2") (pintype "passive"))
      (node (ref "R116") (pin "2") (pinfunction "2_2") (pintype "passive"))
    )
    (net (code "66") (name "Vm") (class "Default")
      (node (ref "C113") (pin "2") (pinfunction "2_2") (pintype "passive"))
      (node (ref "C114") (pin "2") (pinfunction "2_2") (pintype "passive"))
      (node (ref "U102") (pin "13") (pinfunction "VM2_13") (pintype "power_in"))
      (node (ref "U102") (pin "14") (pinfunction "VM3_14") (pintype "power_in"))
      (node (ref "U102") (pin "24") (pinfunction "VM1_24") (pintype "power_in"))
    )
    (net (code "67") (name "unconnected-(IC100-A1-Pad1)") (class "Default")
      (node (ref "IC100") (pin "1") (pinfunction "A1_1") (pintype "passive"))
    )
    (net (code "68") (name "unconnected-(IC100-VT-Pad17)") (class "Default")
      (node (ref "IC100") (pin "17") (pinfunction "VT_17") (pintype "passive"))
    )
    (net (code "69") (name "unconnected-(U100-PA9-Pad30)") (class "Default")
      (node (ref "U100") (pin "30") (pinfunction "PA9_30") (pintype "passive"))
    )
    (net (code "70") (name "unconnected-(U100-PC13-TAMPER-RT_C-Pad2)") (class "Default")
      (node (ref "U100") (pin "2") (pinfunction "PC13-TAMPER-RT_C_2") (pintype "passive"))
    )
    (net (code "71") (name "unconnected-(U100-PC14-OSC32_IN-Pad3)") (class "Default")
      (node (ref "U100") (pin "3") (pinfunction "PC14-OSC32_IN_3") (pintype "passive"))
    )
    (net (code "72") (name "unconnected-(U100-PC15-OSC32_OUT-Pad4)") (class "Default")
      (node (ref "U100") (pin "4") (pinfunction "PC15-OSC32_OUT_4") (pintype "passive"))
    )
    (net (code "73") (name "unconnected-(U100-VBAT-Pad1)") (class "Default")
      (node (ref "U100") (pin "1") (pinfunction "VBAT_1") (pintype "passive"))
    )
    (net (code "74") (name "unconnected-(U101-GPIO4-Pad19)") (class "Default")
      (node (ref "U101") (pin "19") (pinfunction "GPIO4_19") (pintype "passive"))
    )
    (net (code "75") (name "unconnected-(U101-GPIO5-Pad20)") (class "Default")
      (node (ref "U101") (pin "20") (pinfunction "GPIO5_20") (pintype "passive"))
    )
    (net (code "76") (name "unconnected-(U101-GPIO9{slash}SD_D2-Pad11)") (class "Default")
      (node (ref "U101") (pin "11") (pinfunction "GPIO9/SD_D2_11") (pintype "passive"))
    )
    (net (code "77") (name "unconnected-(U101-GPIO10{slash}SPI_CS{slash}SD_D3-Pad12)") (class "Default")
      (node (ref "U101") (pin "12") (pinfunction "GPIO10/SPI_CS/SD_D3_12") (pintype "passive"))
    )
    (net (code "78") (name "unconnected-(U101-GPIO12{slash}HSPIQ-Pad6)") (class "Default")
      (node (ref "U101") (pin "6") (pinfunction "GPIO12/HSPIQ_6") (pintype "passive"))
    )
    (net (code "79") (name "unconnected-(U101-GPIO13{slash}HSPID{slash}CTS0{slash}RXD2-Pad7)") (class "Default")
      (node (ref "U101") (pin "7") (pinfunction "GPIO13/HSPID/CTS0/RXD2_7") (pintype "passive"))
    )
    (net (code "80") (name "unconnected-(U101-GPIO14{slash}HSPICLK-Pad5)") (class "Default")
      (node (ref "U101") (pin "5") (pinfunction "GPIO14/HSPICLK_5") (pintype "passive"))
    )
    (net (code "81") (name "unconnected-(U101-GPIO16{slash}~{WAKE}-Pad4)") (class "Default")
      (node (ref "U101") (pin "4") (pinfunction "GPIO16/~{WAKE}_4") (pintype "passive"))
    )
    (net (code "82") (name "unconnected-(U101-SPI_CLK{slash}SD_CLK-Pad14)") (class "Default")
      (node (ref "U101") (pin "14") (pinfunction "SPI_CLK/SD_CLK_14") (pintype "passive"))
    )
    (net (code "83") (name "unconnected-(U101-SPI_INT{slash}SD_D1-Pad13)") (class "Default")
      (node (ref "U101") (pin "13") (pinfunction "SPI_INT/SD_D1_13") (pintype "passive"))
    )
    (net (code "84") (name "unconnected-(U101-SPI_MISO{slash}SD_D0-Pad10)") (class "Default")
      (node (ref "U101") (pin "10") (pinfunction "SPI_MISO/SD_D0_10") (pintype "passive"))
    )
    (net (code "85") (name "unconnected-(U101-SPI_MOSI{slash}SD_CMD-Pad9)") (class "Default")
      (node (ref "U101") (pin "9") (pinfunction "SPI_MOSI/SD_CMD_9") (pintype "passive"))
    )
    (net (code "86") (name "unconnected-(U102-AO1@2-Pad2)") (class "Default")
      (node (ref "U102") (pin "2") (pinfunction "AO1@2_2") (pintype "output"))
    )
    (net (code "87") (name "unconnected-(U102-AO2@2-Pad6)") (class "Default")
      (node (ref "U102") (pin "6") (pinfunction "AO2@2_6") (pintype "output"))
    )
    (net (code "88") (name "unconnected-(U102-BO1@2-Pad12)") (class "Default")
      (node (ref "U102") (pin "12") (pinfunction "BO1@2_12") (pintype "output"))
    )
    (net (code "89") (name "unconnected-(U102-BO2@2-Pad8)") (class "Default")
      (node (ref "U102") (pin "8") (pinfunction "BO2@2_8") (pintype "output"))
    )
    (net (code "90") (name "unconnected-(U103-CTS#-Pad9)") (class "Default")
      (node (ref "U103") (pin "9") (pinfunction "CTS#_9") (pintype "passive+no_connect"))
    )
    (net (code "91") (name "unconnected-(U103-DCD#-Pad12)") (class "Default")
      (node (ref "U103") (pin "12") (pinfunction "DCD#_12") (pintype "passive+no_connect"))
    )
    (net (code "92") (name "unconnected-(U103-DSR#-Pad10)") (class "Default")
      (node (ref "U103") (pin "10") (pinfunction "DSR#_10") (pintype "passive+no_connect"))
    )
    (net (code "93") (name "unconnected-(U103-NC-Pad7)") (class "Default")
      (node (ref "U103") (pin "7") (pinfunction "NC_7") (pintype "passive+no_connect"))
    )
    (net (code "94") (name "unconnected-(U103-NC-Pad8)") (class "Default")
      (node (ref "U103") (pin "8") (pinfunction "NC_8") (pintype "passive+no_connect"))
    )
    (net (code "95") (name "unconnected-(U103-R232-Pad15)") (class "Default")
      (node (ref "U103") (pin "15") (pinfunction "R232_15") (pintype "passive+no_connect"))
    )
    (net (code "96") (name "unconnected-(U103-RI#-Pad11)") (class "Default")
      (node (ref "U103") (pin "11") (pinfunction "RI#_11") (pintype "passive+no_connect"))
    )
    (net (code "97") (name "unconnected-(USB100-ID-Pad4)") (class "Default")
      (node (ref "USB100") (pin "4") (pinfunction "ID_4") (pintype "passive+no_connect"))
    )
  )
)
